# openSX70_ALPHA_V6-2-1-20181102.net
KiCad netlist of a schematic drawn in EAGLE
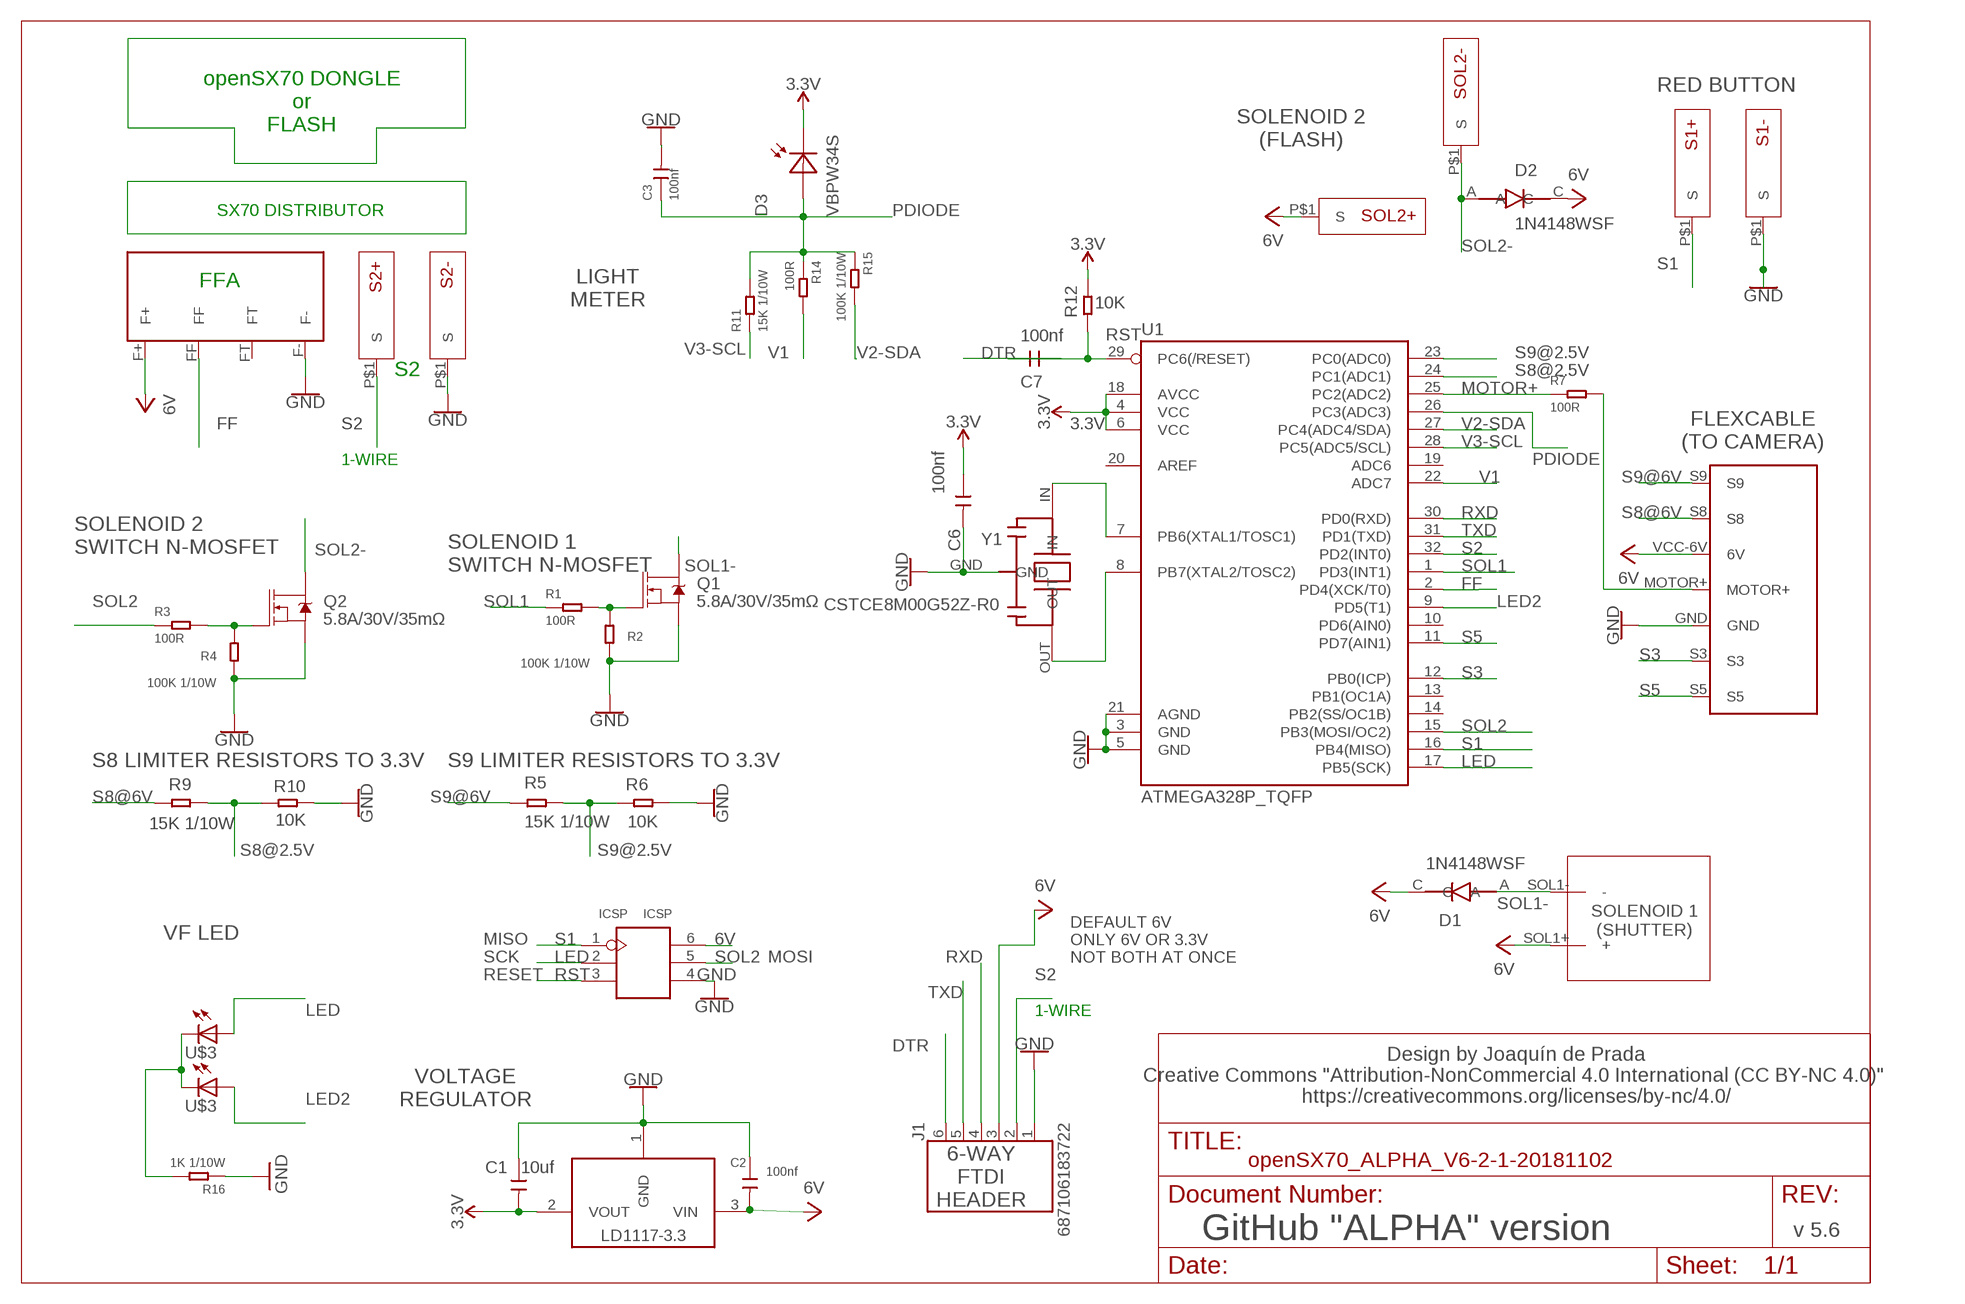
[diagram p0: schematic, sheet 1]

(export (version "E")
  (design (tool "Eeschema 10.0.6"))
  (components
    (comp (ref "C1")
      (value "10uf")
      (footprint "eagle-import:C0603")
      (fields (field (name "MPN") "CC0603KRX5R6BB106"))
      (libsource (lib "eagle-import") (part "CERAMIC-10UF-10V-10%-X5R(0603)"))
    )
    (comp (ref "C2")
      (value "100nf")
      (footprint "eagle-import:C0603")
      (fields (field (name "MPN") "CC0603KRX7R9BB104"))
      (libsource (lib "eagle-import") (part "CERAMIC-100NF-50V-10%-X7R(0603)"))
    )
    (comp (ref "C3")
      (value "100nf")
      (footprint "eagle-import:C0603")
      (fields (field (name "MPN") "CC0603KRX7R9BB104"))
      (libsource (lib "eagle-import") (part "CERAMIC-100NF-50V-10%-X7R(0603)"))
    )
    (comp (ref "C6")
      (value "100nf")
      (footprint "eagle-import:C0603")
      (fields (field (name "MPN") "CC0603KRX7R9BB104"))
      (libsource (lib "eagle-import") (part "CERAMIC-100NF-50V-10%-X7R(0603)"))
    )
    (comp (ref "C7")
      (value "100nf")
      (footprint "eagle-import:C0603")
      (fields (field (name "MPN") "CC0603KRX7R9BB104"))
      (libsource (lib "eagle-import") (part "CERAMIC-100NF-50V-10%-X7R(0603)"))
    )
    (comp (ref "D1")
      (value "1N4148WSF")
      (footprint "eagle-import:SODFL2512X100N")
      (fields (field (name "MANUFACTURER") "Fairchild Semiconductor"))
      (libsource (lib "eagle-import") (part "1N4148WS"))
    )
    (comp (ref "D2")
      (value "1N4148WSF")
      (footprint "eagle-import:SODFL2512X100N")
      (fields (field (name "MANUFACTURER") "Fairchild Semiconductor"))
      (libsource (lib "eagle-import") (part "1N4148WS"))
    )
    (comp (ref "D3")
      (value "VBPW34S")
      (footprint "eagle-import:SOD6439X130N")
      (fields (field (name "DIGI-KEY_PART_NUMBER") "751-1500-1-ND") (field (name "MF") "Vishay"))
      (libsource (lib "eagle-import") (part "VBPW34S"))
    )
    (comp (ref "ICSP")
      (value "ICSP")
      (footprint "eagle-import:H2X3-2.54")
      (libsource (lib "eagle-import") (part "ICSP"))
    )
    (comp (ref "J1")
      (value "687106183722")
      (footprint "eagle-import:687106183722")
      (fields (field (name "MF") "Wurth Electronics"))
      (libsource (lib "eagle-import") (part "687106183722"))
    )
    (comp (ref "LD11172.5V")
      (value "LD1117 2.5V")
      (footprint "eagle-import:SOT223")
      (fields (field (name "MF") "Advanced Monolithic Systems") (field (name "MP") "AMS1117-5.0"))
      (libsource (lib "eagle-import") (part "LD1117-3.3"))
    )
    (comp (ref "Q1")
      (value "5.8A/30V/35mΩ")
      (footprint "eagle-import:SOT23-3")
      (libsource (lib "eagle-import") (part "MOSFET-NCH-AO3404A"))
    )
    (comp (ref "Q2")
      (value "5.8A/30V/35mΩ")
      (footprint "eagle-import:SOT23-3")
      (libsource (lib "eagle-import") (part "MOSFET-NCH-AO3404A"))
    )
    (comp (ref "R1")
      (value "100R")
      (footprint "eagle-import:R0603")
      (fields (field (name "MPN") "RC0603JR-07100RL"))
      (libsource (lib "eagle-import") (part "SMD-RES-100R-5%-1/10W(0603)"))
    )
    (comp (ref "R2")
      (value "100K 1/10W")
      (footprint "eagle-import:R0603")
      (fields (field (name "MPN") "RC0603JR-07100KL"))
      (libsource (lib "eagle-import") (part "SMD-RES-100K-5%-1/10W(0603)"))
    )
    (comp (ref "R3")
      (value "100R")
      (footprint "eagle-import:R0603")
      (fields (field (name "MPN") "RC0603JR-07100RL"))
      (libsource (lib "eagle-import") (part "SMD-RES-100R-5%-1/10W(0603)"))
    )
    (comp (ref "R4")
      (value "100K 1/10W")
      (footprint "eagle-import:R0603")
      (fields (field (name "MPN") "RC0603JR-07100KL"))
      (libsource (lib "eagle-import") (part "SMD-RES-100K-5%-1/10W(0603)"))
    )
    (comp (ref "R5")
      (value "15K 1/10W")
      (footprint "eagle-import:R0603")
      (fields (field (name "MPN") "RC0603FR-0715KL"))
      (libsource (lib "eagle-import") (part "SMD-RES-15K-1%-1/10W(0603)"))
    )
    (comp (ref "R6")
      (value "10K")
      (footprint "eagle-import:R0603")
      (fields (field (name "MPN") "RC0603FR-0710KL"))
      (libsource (lib "eagle-import") (part "SMD-RES-10K-1%-1/10W(0603)"))
    )
    (comp (ref "R7")
      (value "100R")
      (footprint "eagle-import:R0603")
      (fields (field (name "MPN") "RC0603JR-07100RL"))
      (libsource (lib "eagle-import") (part "SMD-RES-100R-5%-1/10W(0603)"))
    )
    (comp (ref "R9")
      (value "15K 1/10W")
      (footprint "eagle-import:R0603")
      (fields (field (name "MPN") "RC0603FR-0715KL"))
      (libsource (lib "eagle-import") (part "SMD-RES-15K-1%-1/10W(0603)"))
    )
    (comp (ref "R10")
      (value "10K")
      (footprint "eagle-import:R0603")
      (fields (field (name "MPN") "RC0603FR-0710KL"))
      (libsource (lib "eagle-import") (part "SMD-RES-10K-1%-1/10W(0603)"))
    )
    (comp (ref "R11")
      (value "15K 1/10W")
      (footprint "eagle-import:R0603")
      (fields (field (name "MPN") "RC0603FR-0715KL"))
      (libsource (lib "eagle-import") (part "SMD-RES-15K-1%-1/10W(0603)"))
    )
    (comp (ref "R12")
      (value "10K")
      (footprint "eagle-import:R0603")
      (fields (field (name "MPN") "RC0603FR-0710KL"))
      (libsource (lib "eagle-import") (part "SMD-RES-10K-1%-1/10W(0603)"))
    )
    (comp (ref "R14")
      (value "100R")
      (footprint "eagle-import:R0603")
      (fields (field (name "MPN") "RC0603JR-07100RL"))
      (libsource (lib "eagle-import") (part "SMD-RES-100R-5%-1/10W(0603)"))
    )
    (comp (ref "R15")
      (value "100K 1/10W")
      (footprint "eagle-import:R0603")
      (fields (field (name "MPN") "RC0603JR-07100KL"))
      (libsource (lib "eagle-import") (part "SMD-RES-100K-5%-1/10W(0603)"))
    )
    (comp (ref "R16")
      (value "1K 1/10W")
      (footprint "eagle-import:R0603")
      (fields (field (name "MPN") "RC0603JR-071KL"))
      (libsource (lib "eagle-import") (part "SMD-RES-1K-5%-1/10W(0603)"))
    )
    (comp (ref "S1+")
      (value "SX70-S-PAD-NEW")
      (footprint "eagle-import:SX70-S-PAD2")
      (libsource (lib "eagle-import") (part "SX70-S-PAD-NEW"))
    )
    (comp (ref "S1-")
      (value "SX70-S-PAD-NEW")
      (footprint "eagle-import:SX70-S-PAD2")
      (libsource (lib "eagle-import") (part "SX70-S-PAD-NEW"))
    )
    (comp (ref "S2+")
      (value "SX70-S-PAD-NEW")
      (footprint "eagle-import:SX70-S-PAD2")
      (libsource (lib "eagle-import") (part "SX70-S-PAD-NEW"))
    )
    (comp (ref "S2-")
      (value "SX70-S-PAD-NEW")
      (footprint "eagle-import:SX70-S-PAD2")
      (libsource (lib "eagle-import") (part "SX70-S-PAD-NEW"))
    )
    (comp (ref "SOL1")
      (value "SX70-SOLENOID1-2PADS")
      (footprint "eagle-import:SX70-SOLENOID1-2")
      (libsource (lib "eagle-import") (part "SX70-SOLENOID1-2PADS"))
    )
    (comp (ref "SOL2+")
      (value "SX70-S-PAD-NEW")
      (footprint "eagle-import:SX70-S-PAD2")
      (libsource (lib "eagle-import") (part "SX70-S-PAD-NEW"))
    )
    (comp (ref "SOL2-")
      (value "SX70-S-PAD-NEW")
      (footprint "eagle-import:SX70-S-PAD2")
      (libsource (lib "eagle-import") (part "SX70-S-PAD-NEW"))
    )
    (comp (ref "U$1")
      (value "SX70-7-PAD")
      (footprint "eagle-import:SX70-7-PAD")
      (libsource (lib "eagle-import") (part "SX70-7-PAD"))
    )
    (comp (ref "U$2")
      (value "FFA")
      (footprint "eagle-import:FFA-PAD-PACKAGE")
      (libsource (lib "eagle-import") (part "SX70-FFA-PAD"))
    )
    (comp (ref "U$3")
      (value "DUAL-LED-0603-BIS")
      (footprint "eagle-import:LED_APHB1608SYKSURKC")
      (libsource (lib "eagle-import") (part "DUAL-LED-0603-BIS"))
    )
    (comp (ref "U1")
      (value "ATMEGA328P_TQFP")
      (footprint "eagle-import:TQFP32-08")
      (libsource (lib "eagle-import") (part "ATMEGA328P_TQFP"))
    )
    (comp (ref "Y1")
      (value "CSTCE8M00G52Z-R0")
      (footprint "eagle-import:CFP95P160X100-3N")
      (fields (field (name "MF") "Murata") (field (name "MP") "CSTCE16M0V53-R0"))
      (libsource (lib "eagle-import") (part "CSTCE16M0V53-R0"))
    )
  )
  (nets
    (net (code "1") (name "/DTR") (class "Default")
      (node (ref "C7") (pin "1") (pinfunction "1_1") (pintype "passive"))
      (node (ref "J1") (pin "6") (pinfunction "1_6") (pintype "passive"))
    )
    (net (code "2") (name "/FF") (class "Default")
      (node (ref "U$2") (pin "FF") (pinfunction "FF_FF") (pintype "bidirectional"))
      (node (ref "U1") (pin "2") (pinfunction "PD4(XCK/T0)_2") (pintype "bidirectional"))
    )
    (net (code "3") (name "/LED") (class "Default")
      (node (ref "ICSP") (pin "2") (pinfunction "SCK_2") (pintype "bidirectional"))
      (node (ref "U$3") (pin "1") (pinfunction "A_1") (pintype "passive"))
      (node (ref "U1") (pin "17") (pinfunction "PB5(SCK)_17") (pintype "bidirectional"))
    )
    (net (code "4") (name "/LED2") (class "Default")
      (node (ref "U$3") (pin "3") (pinfunction "A1_3") (pintype "passive"))
      (node (ref "U1") (pin "9") (pinfunction "PD5(T1)_9") (pintype "bidirectional"))
    )
    (net (code "5") (name "/MOTOR+") (class "Default")
      (node (ref "R7") (pin "1") (pinfunction "1_1") (pintype "passive"))
      (node (ref "U1") (pin "25") (pinfunction "PC2(ADC2)_25") (pintype "bidirectional"))
    )
    (net (code "6") (name "/PDIODE") (class "Default")
      (node (ref "C3") (pin "1") (pinfunction "1_1") (pintype "passive"))
      (node (ref "D3") (pin "A") (pinfunction "A_A") (pintype "passive"))
      (node (ref "R11") (pin "2") (pinfunction "2_2") (pintype "passive"))
      (node (ref "R14") (pin "1") (pinfunction "1_1") (pintype "passive"))
      (node (ref "R15") (pin "1") (pinfunction "1_1") (pintype "passive"))
      (node (ref "U1") (pin "26") (pinfunction "PC3(ADC3)_26") (pintype "bidirectional"))
    )
    (net (code "7") (name "/RST") (class "Default")
      (node (ref "C7") (pin "2") (pinfunction "2_2") (pintype "passive"))
      (node (ref "ICSP") (pin "3") (pinfunction "RST_3") (pintype "bidirectional"))
      (node (ref "R12") (pin "1") (pinfunction "1_1") (pintype "passive"))
      (node (ref "U1") (pin "29") (pinfunction "PC6(/RESET)_29") (pintype "bidirectional"))
    )
    (net (code "8") (name "/RXD") (class "Default")
      (node (ref "J1") (pin "4") (pinfunction "3_4") (pintype "passive"))
      (node (ref "U1") (pin "30") (pinfunction "PD0(RXD)_30") (pintype "bidirectional"))
    )
    (net (code "9") (name "/S1") (class "Default")
      (node (ref "ICSP") (pin "1") (pinfunction "MISO_1") (pintype "bidirectional"))
      (node (ref "S1+") (pin "P$1") (pinfunction "S_P$1") (pintype "bidirectional"))
      (node (ref "U1") (pin "16") (pinfunction "PB4(MISO)_16") (pintype "bidirectional"))
    )
    (net (code "10") (name "/S2") (class "Default")
      (node (ref "J1") (pin "2") (pinfunction "5_2") (pintype "passive"))
      (node (ref "S2+") (pin "P$1") (pinfunction "S_P$1") (pintype "bidirectional"))
      (node (ref "U1") (pin "32") (pinfunction "PD2(INT0)_32") (pintype "bidirectional"))
    )
    (net (code "11") (name "/S3") (class "Default")
      (node (ref "U$1") (pin "S3") (pinfunction "S3_S3") (pintype "bidirectional"))
      (node (ref "U1") (pin "12") (pinfunction "PB0(ICP)_12") (pintype "bidirectional"))
    )
    (net (code "12") (name "/S5") (class "Default")
      (node (ref "U$1") (pin "S5") (pinfunction "S5_S5") (pintype "bidirectional"))
      (node (ref "U1") (pin "11") (pinfunction "PD7(AIN1)_11") (pintype "bidirectional"))
    )
    (net (code "13") (name "/S8@2.5V") (class "Default")
      (node (ref "R10") (pin "1") (pinfunction "1_1") (pintype "passive"))
      (node (ref "R9") (pin "2") (pinfunction "2_2") (pintype "passive"))
      (node (ref "U1") (pin "24") (pinfunction "PC1(ADC1)_24") (pintype "bidirectional"))
    )
    (net (code "14") (name "/S8@6V") (class "Default")
      (node (ref "R9") (pin "1") (pinfunction "1_1") (pintype "passive"))
      (node (ref "U$1") (pin "S8") (pinfunction "S8_S8") (pintype "bidirectional"))
    )
    (net (code "15") (name "/S9@2.5V") (class "Default")
      (node (ref "R5") (pin "2") (pinfunction "2_2") (pintype "passive"))
      (node (ref "R6") (pin "1") (pinfunction "1_1") (pintype "passive"))
      (node (ref "U1") (pin "23") (pinfunction "PC0(ADC0)_23") (pintype "bidirectional"))
    )
    (net (code "16") (name "/S9@6V") (class "Default")
      (node (ref "R5") (pin "1") (pinfunction "1_1") (pintype "passive"))
      (node (ref "U$1") (pin "S9") (pinfunction "S9_S9") (pintype "bidirectional"))
    )
    (net (code "17") (name "/SOL1") (class "Default")
      (node (ref "R1") (pin "1") (pinfunction "1_1") (pintype "passive"))
      (node (ref "U1") (pin "1") (pinfunction "PD3(INT1)_1") (pintype "bidirectional"))
    )
    (net (code "18") (name "/SOL1-") (class "Default")
      (node (ref "D1") (pin "A") (pinfunction "A_A") (pintype "passive"))
      (node (ref "Q1") (pin "3") (pinfunction "D_3") (pintype "bidirectional"))
      (node (ref "SOL1") (pin "SOL1-") (pinfunction "-_SOL1-") (pintype "bidirectional"))
    )
    (net (code "19") (name "/SOL2") (class "Default")
      (node (ref "ICSP") (pin "5") (pinfunction "MOSI_5") (pintype "bidirectional"))
      (node (ref "R3") (pin "1") (pinfunction "1_1") (pintype "passive"))
      (node (ref "U1") (pin "15") (pinfunction "PB3(MOSI/OC2)_15") (pintype "bidirectional"))
    )
    (net (code "20") (name "/SOL2-") (class "Default")
      (node (ref "D2") (pin "A") (pinfunction "A_A") (pintype "passive"))
      (node (ref "Q2") (pin "3") (pinfunction "D_3") (pintype "bidirectional"))
      (node (ref "SOL2-") (pin "P$1") (pinfunction "S_P$1") (pintype "bidirectional"))
    )
    (net (code "21") (name "/TXD") (class "Default")
      (node (ref "J1") (pin "5") (pinfunction "2_5") (pintype "passive"))
      (node (ref "U1") (pin "31") (pinfunction "PD1(TXD)_31") (pintype "bidirectional"))
    )
    (net (code "22") (name "/V1") (class "Default")
      (node (ref "R14") (pin "2") (pinfunction "2_2") (pintype "passive"))
      (node (ref "U1") (pin "22") (pinfunction "ADC7_22") (pintype "bidirectional"))
    )
    (net (code "23") (name "/V2-SDA") (class "Default")
      (node (ref "R15") (pin "2") (pinfunction "2_2") (pintype "passive"))
      (node (ref "U1") (pin "27") (pinfunction "PC4(ADC4/SDA)_27") (pintype "bidirectional"))
    )
    (net (code "24") (name "/V3-SCL") (class "Default")
      (node (ref "R11") (pin "1") (pinfunction "1_1") (pintype "passive"))
      (node (ref "U1") (pin "28") (pinfunction "PC5(ADC5/SCL)_28") (pintype "bidirectional"))
    )
    (net (code "25") (name "3.3V") (class "Default")
      (node (ref "C1") (pin "2") (pinfunction "2_2") (pintype "passive"))
      (node (ref "C6") (pin "1") (pinfunction "1_1") (pintype "passive"))
      (node (ref "D3") (pin "C") (pinfunction "C_C") (pintype "passive"))
      (node (ref "LD11172.5V") (pin "2") (pinfunction "VOUT_2") (pintype "bidirectional"))
      (node (ref "R12") (pin "2") (pinfunction "2_2") (pintype "passive"))
      (node (ref "U1") (pin "18") (pinfunction "AVCC_18") (pintype "bidirectional"))
      (node (ref "U1") (pin "4") (pinfunction "VCC_4") (pintype "bidirectional"))
      (node (ref "U1") (pin "6") (pinfunction "VCC_6") (pintype "bidirectional"))
    )
    (net (code "26") (name "6V") (class "Default")
      (node (ref "C2") (pin "2") (pinfunction "2_2") (pintype "passive"))
      (node (ref "D1") (pin "C") (pinfunction "C_C") (pintype "passive"))
      (node (ref "D2") (pin "C") (pinfunction "C_C") (pintype "passive"))
      (node (ref "ICSP") (pin "6") (pinfunction "VCC_6") (pintype "bidirectional"))
      (node (ref "J1") (pin "3") (pinfunction "4_3") (pintype "passive"))
      (node (ref "LD11172.5V") (pin "3") (pinfunction "VIN_3") (pintype "bidirectional"))
      (node (ref "SOL1") (pin "SOL1+") (pinfunction "+_SOL1+") (pintype "bidirectional"))
      (node (ref "SOL2+") (pin "P$1") (pinfunction "S_P$1") (pintype "bidirectional"))
      (node (ref "U$1") (pin "VCC-6V") (pinfunction "6V_VCC-6V") (pintype "bidirectional"))
      (node (ref "U$2") (pin "F+") (pinfunction "F+_F+") (pintype "bidirectional"))
    )
    (net (code "27") (name "GND") (class "Default")
      (node (ref "C1") (pin "1") (pinfunction "1_1") (pintype "passive"))
      (node (ref "C2") (pin "1") (pinfunction "1_1") (pintype "passive"))
      (node (ref "C3") (pin "2") (pinfunction "2_2") (pintype "passive"))
      (node (ref "C6") (pin "2") (pinfunction "2_2") (pintype "passive"))
      (node (ref "ICSP") (pin "4") (pinfunction "GND_4") (pintype "bidirectional"))
      (node (ref "J1") (pin "1") (pinfunction "6_1") (pintype "passive"))
      (node (ref "LD11172.5V") (pin "1") (pinfunction "GND_1") (pintype "bidirectional"))
      (node (ref "Q1") (pin "2") (pinfunction "S_2") (pintype "bidirectional"))
      (node (ref "Q2") (pin "2") (pinfunction "S_2") (pintype "bidirectional"))
      (node (ref "R10") (pin "2") (pinfunction "2_2") (pintype "passive"))
      (node (ref "R16") (pin "1") (pinfunction "1_1") (pintype "passive"))
      (node (ref "R2") (pin "1") (pinfunction "1_1") (pintype "passive"))
      (node (ref "R4") (pin "1") (pinfunction "1_1") (pintype "passive"))
      (node (ref "R6") (pin "2") (pinfunction "2_2") (pintype "passive"))
      (node (ref "S1-") (pin "P$1") (pinfunction "S_P$1") (pintype "bidirectional"))
      (node (ref "S2-") (pin "P$1") (pinfunction "S_P$1") (pintype "bidirectional"))
      (node (ref "U$1") (pin "GND") (pinfunction "GND_GND") (pintype "bidirectional"))
      (node (ref "U$2") (pin "F-") (pinfunction "F-_F-") (pintype "bidirectional"))
      (node (ref "U1") (pin "21") (pinfunction "AGND_21") (pintype "bidirectional"))
      (node (ref "U1") (pin "3") (pinfunction "GND_3") (pintype "bidirectional"))
      (node (ref "U1") (pin "5") (pinfunction "GND_5") (pintype "bidirectional"))
      (node (ref "Y1") (pin "GND") (pinfunction "GND_GND") (pintype "passive"))
    )
    (net (code "28") (name "Net-(Q1-G)") (class "Default")
      (node (ref "Q1") (pin "1") (pinfunction "G_1") (pintype "bidirectional"))
      (node (ref "R1") (pin "2") (pinfunction "2_2") (pintype "passive"))
      (node (ref "R2") (pin "2") (pinfunction "2_2") (pintype "passive"))
    )
    (net (code "29") (name "Net-(Q2-G)") (class "Default")
      (node (ref "Q2") (pin "1") (pinfunction "G_1") (pintype "bidirectional"))
      (node (ref "R3") (pin "2") (pinfunction "2_2") (pintype "passive"))
      (node (ref "R4") (pin "2") (pinfunction "2_2") (pintype "passive"))
    )
    (net (code "30") (name "Net-(R7-Pad2)") (class "Default")
      (node (ref "R7") (pin "2") (pinfunction "2_2") (pintype "passive"))
      (node (ref "U$1") (pin "MOTOR+") (pinfunction "MOTOR+_MOTOR+") (pintype "bidirectional"))
    )
    (net (code "31") (name "Net-(U$3-C)") (class "Default")
      (node (ref "R16") (pin "2") (pinfunction "2_2") (pintype "passive"))
      (node (ref "U$3") (pin "2") (pinfunction "C_2") (pintype "passive"))
      (node (ref "U$3") (pin "4") (pinfunction "C1_4") (pintype "passive"))
    )
    (net (code "32") (name "Net-(U1-PB6(XTAL1{slash}TOSC1))") (class "Default")
      (node (ref "U1") (pin "7") (pinfunction "PB6(XTAL1/TOSC1)_7") (pintype "bidirectional"))
      (node (ref "Y1") (pin "IN") (pinfunction "IN_IN") (pintype "input"))
    )
    (net (code "33") (name "Net-(U1-PB7(XTAL2{slash}TOSC2))") (class "Default")
      (node (ref "U1") (pin "8") (pinfunction "PB7(XTAL2/TOSC2)_8") (pintype "bidirectional"))
      (node (ref "Y1") (pin "OUT") (pinfunction "OUT_OUT") (pintype "output"))
    )
    (net (code "34") (name "unconnected-(U$2-PadFT)") (class "Default")
      (node (ref "U$2") (pin "FT") (pinfunction "FT_FT") (pintype "bidirectional"))
    )
    (net (code "35") (name "unconnected-(U1-ADC6-Pad19)") (class "Default")
      (node (ref "U1") (pin "19") (pinfunction "ADC6_19") (pintype "bidirectional"))
    )
    (net (code "36") (name "unconnected-(U1-AREF-Pad20)") (class "Default")
      (node (ref "U1") (pin "20") (pinfunction "AREF_20") (pintype "bidirectional"))
    )
    (net (code "37") (name "unconnected-(U1-PB1(OC1A)-Pad13)") (class "Default")
      (node (ref "U1") (pin "13") (pinfunction "PB1(OC1A)_13") (pintype "bidirectional"))
    )
    (net (code "38") (name "unconnected-(U1-PB2(SS{slash}OC1B)-Pad14)") (class "Default")
      (node (ref "U1") (pin "14") (pinfunction "PB2(SS/OC1B)_14") (pintype "bidirectional"))
    )
    (net (code "39") (name "unconnected-(U1-PD6(AIN0)-Pad10)") (class "Default")
      (node (ref "U1") (pin "10") (pinfunction "PD6(AIN0)_10") (pintype "bidirectional"))
    )
  )
)
